# multiMicro_base_64pin.net
KiCad netlist of a schematic drawn in EAGLE
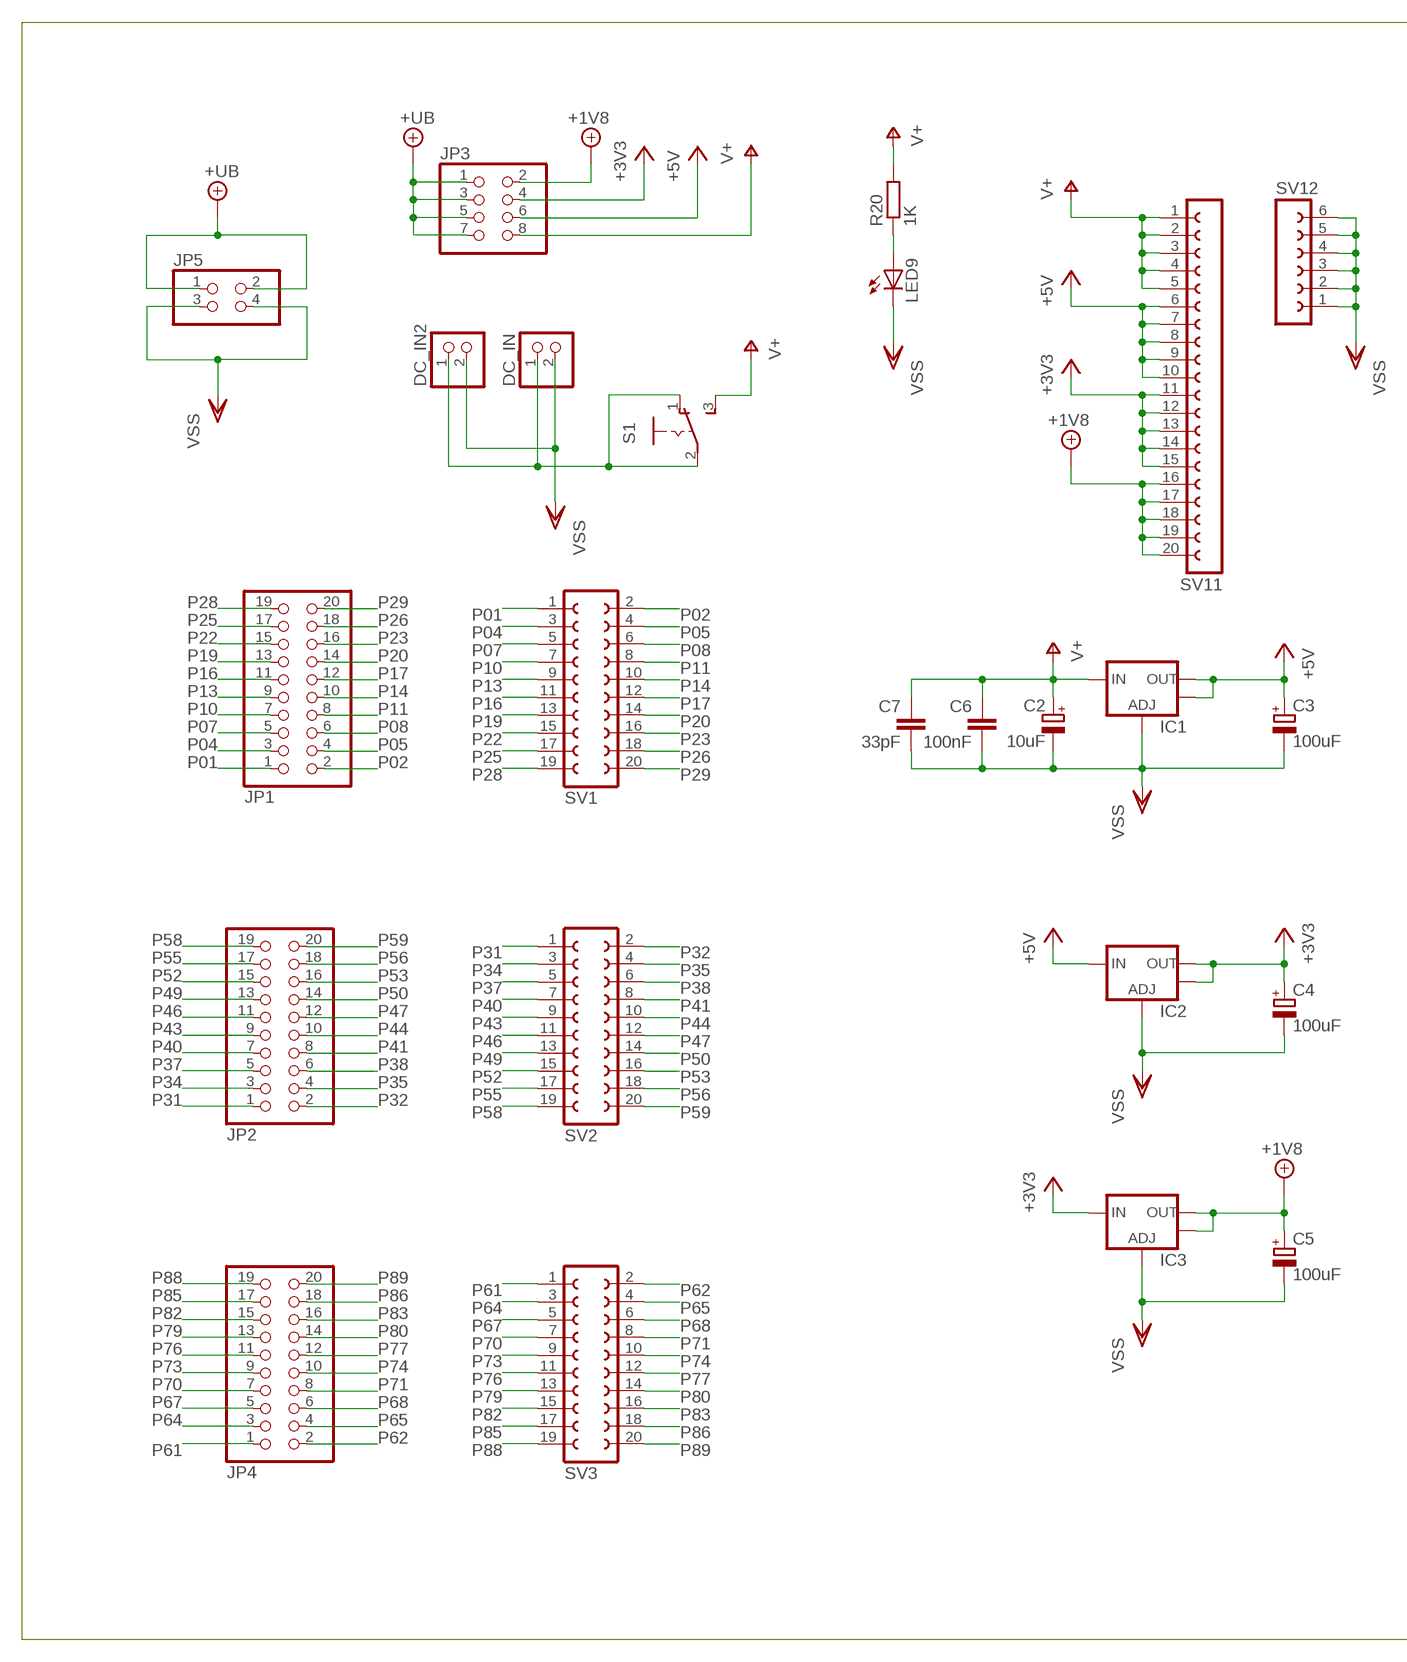
[diagram p0: schematic, sheet 1, part 1 of 2]
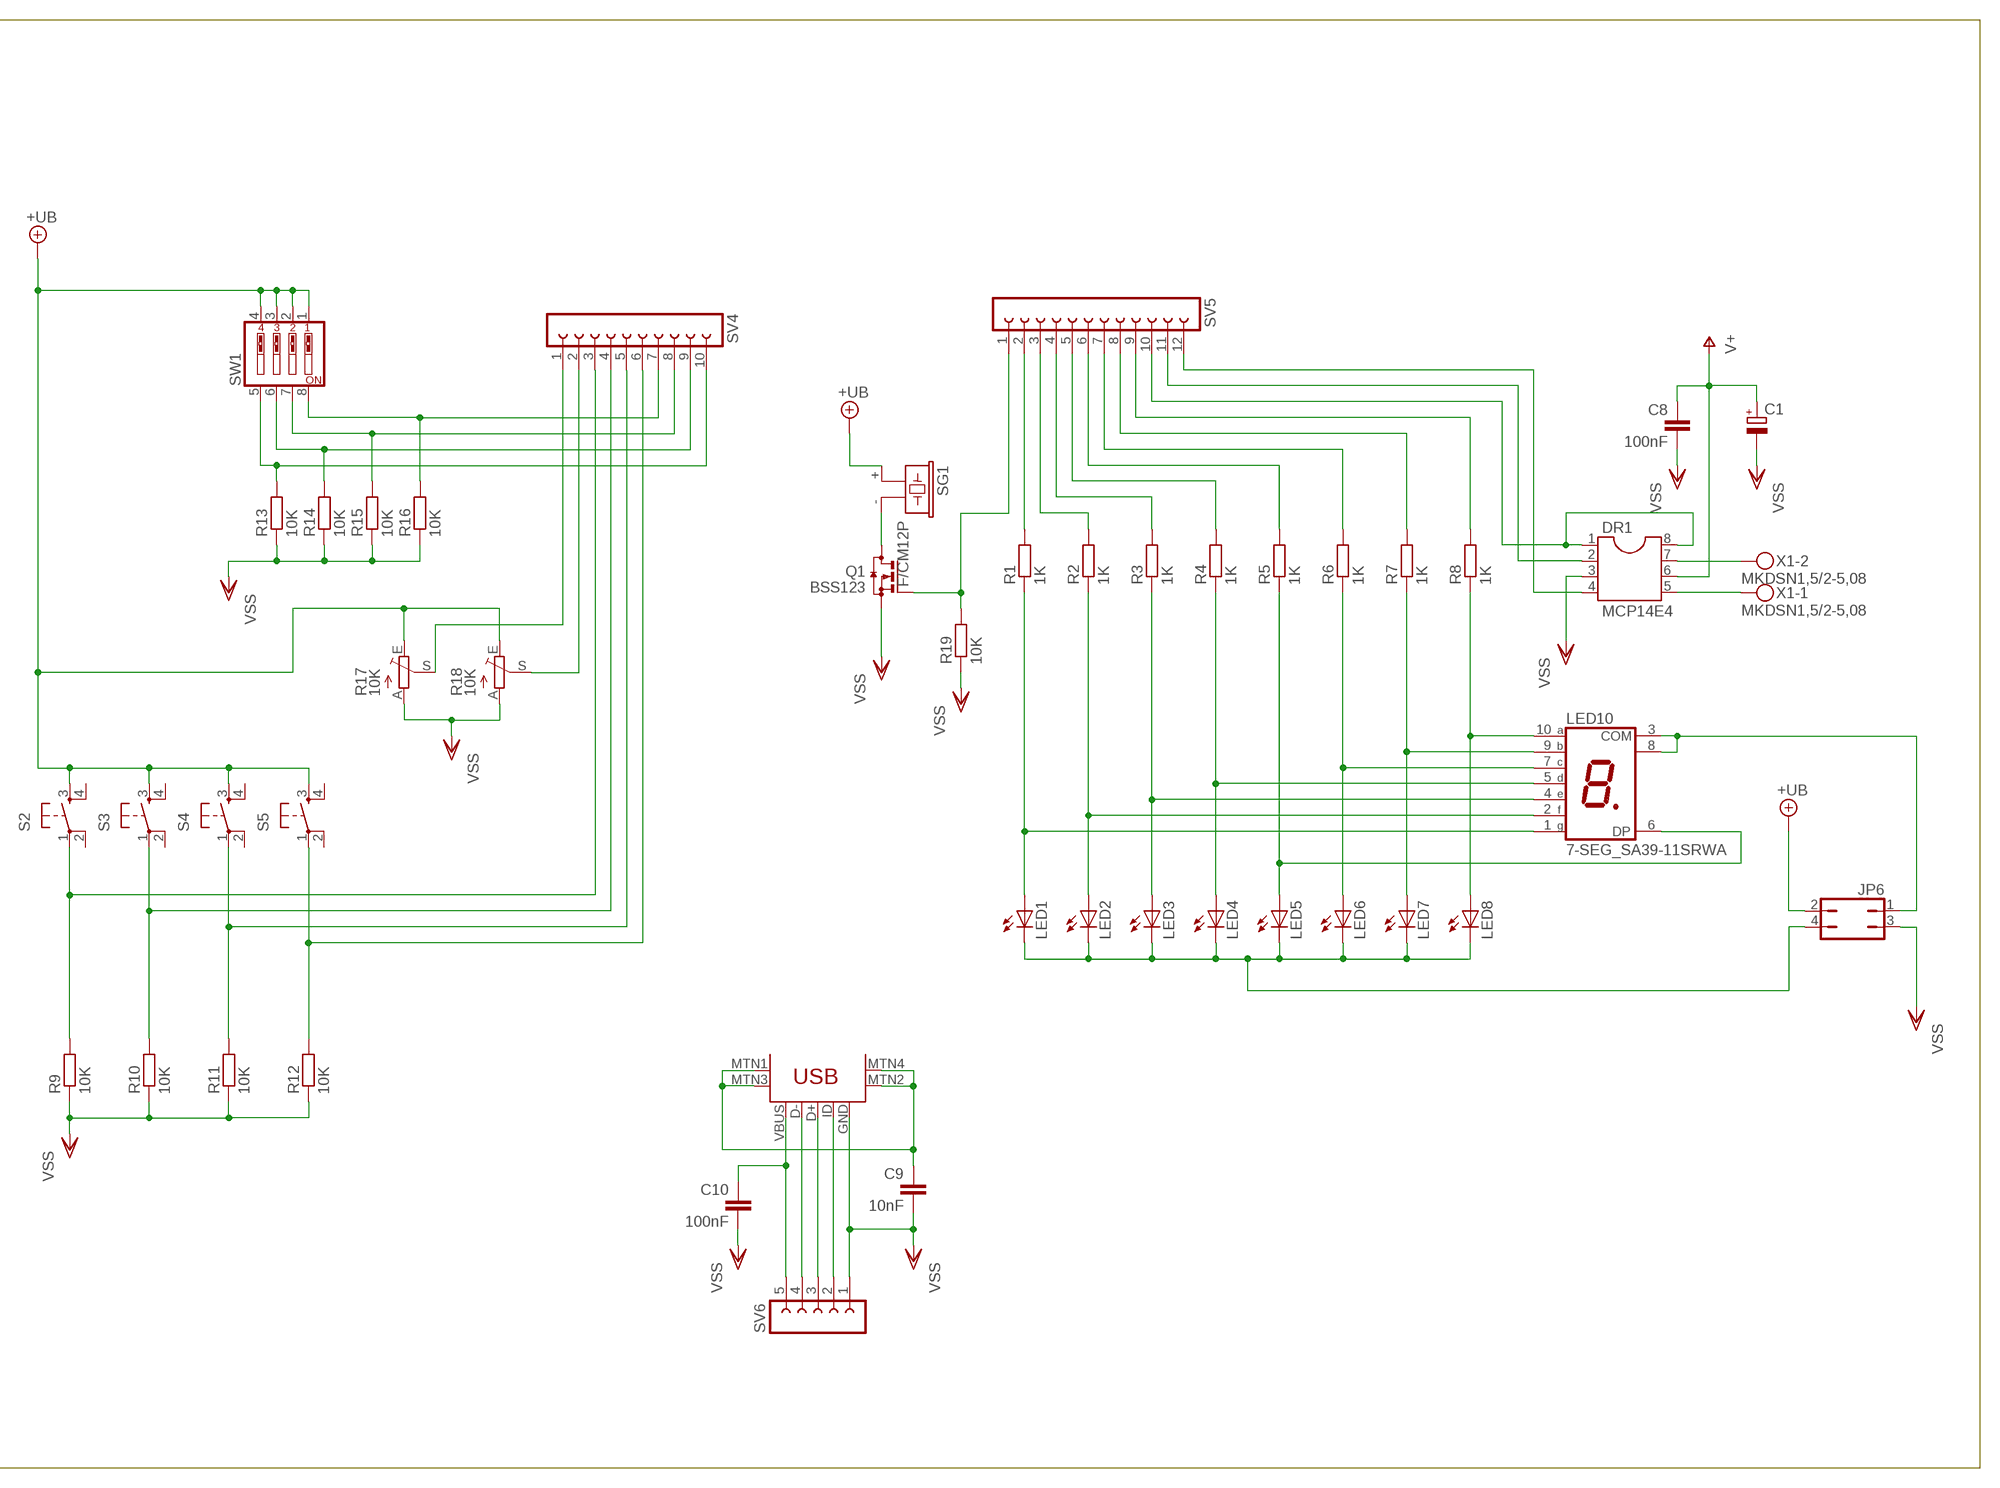
[diagram p1: schematic, sheet 1, part 2 of 2]

(export (version "E")
  (design (tool "Eeschema 10.0.6"))
  (components
    (comp (ref "C1")
      (value "CPOL-EU140CLH-0810")
      (footprint "eagle-import:140CLH-0810")
      (libsource (lib "eagle-import") (part "CPOL-EU140CLH-0810"))
    )
    (comp (ref "C2")
      (value "10uF")
      (footprint "eagle-import:SMC_C")
      (libsource (lib "eagle-import") (part "CPOL-EUSMCC"))
    )
    (comp (ref "C3")
      (value "100uF")
      (footprint "eagle-import:CT7343")
      (libsource (lib "eagle-import") (part "CPOL-EUCT7343"))
    )
    (comp (ref "C4")
      (value "100uF")
      (footprint "eagle-import:CT7343")
      (libsource (lib "eagle-import") (part "CPOL-EUCT7343"))
    )
    (comp (ref "C5")
      (value "100uF")
      (footprint "eagle-import:CT7343")
      (libsource (lib "eagle-import") (part "CPOL-EUCT7343"))
    )
    (comp (ref "C6")
      (value "100nF")
      (footprint "eagle-import:C0805")
      (libsource (lib "eagle-import") (part "C-EUC0805"))
    )
    (comp (ref "C7")
      (value "33pF")
      (footprint "eagle-import:C0805")
      (libsource (lib "eagle-import") (part "C-EUC0805"))
    )
    (comp (ref "C8")
      (value "100nF")
      (footprint "eagle-import:C0805")
      (libsource (lib "eagle-import") (part "C-EUC0805"))
    )
    (comp (ref "C9")
      (value "10nF")
      (footprint "eagle-import:C0805")
      (libsource (lib "eagle-import") (part "C-EUC0805"))
    )
    (comp (ref "C10")
      (value "100nF")
      (footprint "eagle-import:C0805")
      (libsource (lib "eagle-import") (part "C-EUC0805"))
    )
    (comp (ref "DC_IN")
      (value "PINHD-1X2/90")
      (footprint "eagle-import:1X02_90")
      (libsource (lib "eagle-import") (part "PINHD-1X2/90"))
    )
    (comp (ref "DC_IN2")
      (value "PINHD-1X2/90")
      (footprint "eagle-import:1X02_90")
      (libsource (lib "eagle-import") (part "PINHD-1X2/90"))
    )
    (comp (ref "DR1")
      (value "MCP14E4")
      (footprint "eagle-import:SOIC08")
      (libsource (lib "eagle-import") (part "SOIC08"))
    )
    (comp (ref "IC1")
      (value "V_REG_LM1117SOT223")
      (footprint "eagle-import:SOT223")
      (libsource (lib "eagle-import") (part "V_REG_LM1117SOT223"))
    )
    (comp (ref "IC2")
      (value "V_REG_LM1117SOT223")
      (footprint "eagle-import:SOT223")
      (libsource (lib "eagle-import") (part "V_REG_LM1117SOT223"))
    )
    (comp (ref "IC3")
      (value "V_REG_LM1117SOT223")
      (footprint "eagle-import:SOT223")
      (libsource (lib "eagle-import") (part "V_REG_LM1117SOT223"))
    )
    (comp (ref "JP1")
      (value "PINHD-2X10/90")
      (footprint "eagle-import:2X10_90")
      (libsource (lib "eagle-import") (part "PINHD-2X10/90"))
    )
    (comp (ref "JP2")
      (value "PINHD-2X10/90")
      (footprint "eagle-import:2X10_90")
      (libsource (lib "eagle-import") (part "PINHD-2X10/90"))
    )
    (comp (ref "JP3")
      (value "PINHD-2X4")
      (footprint "eagle-import:2X04")
      (libsource (lib "eagle-import") (part "PINHD-2X4"))
    )
    (comp (ref "JP4")
      (value "PINHD-2X10/90")
      (footprint "eagle-import:2X10_90")
      (libsource (lib "eagle-import") (part "PINHD-2X10/90"))
    )
    (comp (ref "JP5")
      (value "PINHD-2X2/90")
      (footprint "eagle-import:2X02_90")
      (libsource (lib "eagle-import") (part "PINHD-2X2/90"))
    )
    (comp (ref "JP6")
      (value "JP2Q")
      (footprint "eagle-import:JP2Q")
      (libsource (lib "eagle-import") (part "JP2Q"))
    )
    (comp (ref "LED1")
      (value "LEDCHIP-LED0805")
      (footprint "eagle-import:CHIP-LED0805")
      (libsource (lib "eagle-import") (part "LEDCHIP-LED0805"))
    )
    (comp (ref "LED2")
      (value "LEDCHIP-LED0805")
      (footprint "eagle-import:CHIP-LED0805")
      (libsource (lib "eagle-import") (part "LEDCHIP-LED0805"))
    )
    (comp (ref "LED3")
      (value "LEDCHIP-LED0805")
      (footprint "eagle-import:CHIP-LED0805")
      (libsource (lib "eagle-import") (part "LEDCHIP-LED0805"))
    )
    (comp (ref "LED4")
      (value "LEDCHIP-LED0805")
      (footprint "eagle-import:CHIP-LED0805")
      (libsource (lib "eagle-import") (part "LEDCHIP-LED0805"))
    )
    (comp (ref "LED5")
      (value "LEDCHIP-LED0805")
      (footprint "eagle-import:CHIP-LED0805")
      (libsource (lib "eagle-import") (part "LEDCHIP-LED0805"))
    )
    (comp (ref "LED6")
      (value "LEDCHIP-LED0805")
      (footprint "eagle-import:CHIP-LED0805")
      (libsource (lib "eagle-import") (part "LEDCHIP-LED0805"))
    )
    (comp (ref "LED7")
      (value "LEDCHIP-LED0805")
      (footprint "eagle-import:CHIP-LED0805")
      (libsource (lib "eagle-import") (part "LEDCHIP-LED0805"))
    )
    (comp (ref "LED8")
      (value "LEDCHIP-LED0805")
      (footprint "eagle-import:CHIP-LED0805")
      (libsource (lib "eagle-import") (part "LEDCHIP-LED0805"))
    )
    (comp (ref "LED9")
      (value "LEDCHIP-LED0805")
      (footprint "eagle-import:CHIP-LED0805")
      (libsource (lib "eagle-import") (part "LEDCHIP-LED0805"))
    )
    (comp (ref "LED10")
      (value "7-SEG_SA39-11SRWA")
      (footprint "eagle-import:SA39-11SRWA")
      (libsource (lib "eagle-import") (part "7-SEG_SA39-11SRWA"))
    )
    (comp (ref "Q1")
      (value "BSS123")
      (footprint "eagle-import:SOT23")
      (libsource (lib "eagle-import") (part "BSS123"))
    )
    (comp (ref "R1")
      (value "1K")
      (footprint "eagle-import:R0805")
      (libsource (lib "eagle-import") (part "R-EU_R0805"))
    )
    (comp (ref "R2")
      (value "1K")
      (footprint "eagle-import:R0805")
      (libsource (lib "eagle-import") (part "R-EU_R0805"))
    )
    (comp (ref "R3")
      (value "1K")
      (footprint "eagle-import:R0805")
      (libsource (lib "eagle-import") (part "R-EU_R0805"))
    )
    (comp (ref "R4")
      (value "1K")
      (footprint "eagle-import:R0805")
      (libsource (lib "eagle-import") (part "R-EU_R0805"))
    )
    (comp (ref "R5")
      (value "1K")
      (footprint "eagle-import:R0805")
      (libsource (lib "eagle-import") (part "R-EU_R0805"))
    )
    (comp (ref "R6")
      (value "1K")
      (footprint "eagle-import:R0805")
      (libsource (lib "eagle-import") (part "R-EU_R0805"))
    )
    (comp (ref "R7")
      (value "1K")
      (footprint "eagle-import:R0805")
      (libsource (lib "eagle-import") (part "R-EU_R0805"))
    )
    (comp (ref "R8")
      (value "1K")
      (footprint "eagle-import:R0805")
      (libsource (lib "eagle-import") (part "R-EU_R0805"))
    )
    (comp (ref "R9")
      (value "10K")
      (footprint "eagle-import:R0805")
      (libsource (lib "eagle-import") (part "R-EU_R0805"))
    )
    (comp (ref "R10")
      (value "10K")
      (footprint "eagle-import:R0805")
      (libsource (lib "eagle-import") (part "R-EU_R0805"))
    )
    (comp (ref "R11")
      (value "10K")
      (footprint "eagle-import:R0805")
      (libsource (lib "eagle-import") (part "R-EU_R0805"))
    )
    (comp (ref "R12")
      (value "10K")
      (footprint "eagle-import:R0805")
      (libsource (lib "eagle-import") (part "R-EU_R0805"))
    )
    (comp (ref "R13")
      (value "10K")
      (footprint "eagle-import:R0805")
      (libsource (lib "eagle-import") (part "R-EU_R0805"))
    )
    (comp (ref "R14")
      (value "10K")
      (footprint "eagle-import:R0805")
      (libsource (lib "eagle-import") (part "R-EU_R0805"))
    )
    (comp (ref "R15")
      (value "10K")
      (footprint "eagle-import:R0805")
      (libsource (lib "eagle-import") (part "R-EU_R0805"))
    )
    (comp (ref "R16")
      (value "10K")
      (footprint "eagle-import:R0805")
      (libsource (lib "eagle-import") (part "R-EU_R0805"))
    )
    (comp (ref "R17")
      (value "10K")
      (footprint "eagle-import:CA6V")
      (libsource (lib "eagle-import") (part "TRIM_EU-CA6V"))
    )
    (comp (ref "R18")
      (value "10K")
      (footprint "eagle-import:CA6V")
      (libsource (lib "eagle-import") (part "TRIM_EU-CA6V"))
    )
    (comp (ref "R19")
      (value "10K")
      (footprint "eagle-import:R0805")
      (libsource (lib "eagle-import") (part "R-EU_R0805"))
    )
    (comp (ref "R20")
      (value "1K")
      (footprint "eagle-import:R0805")
      (libsource (lib "eagle-import") (part "R-EU_R0805"))
    )
    (comp (ref "S1")
      (value "255SB")
      (footprint "eagle-import:255SB")
      (libsource (lib "eagle-import") (part "255SB"))
    )
    (comp (ref "S2")
      (value "TAC_SWITCHPTH")
      (footprint "eagle-import:TACTILE-PTH")
      (libsource (lib "eagle-import") (part "TAC_SWITCHPTH"))
    )
    (comp (ref "S3")
      (value "TAC_SWITCHPTH")
      (footprint "eagle-import:TACTILE-PTH")
      (libsource (lib "eagle-import") (part "TAC_SWITCHPTH"))
    )
    (comp (ref "S4")
      (value "TAC_SWITCHPTH")
      (footprint "eagle-import:TACTILE-PTH")
      (libsource (lib "eagle-import") (part "TAC_SWITCHPTH"))
    )
    (comp (ref "S5")
      (value "TAC_SWITCHPTH")
      (footprint "eagle-import:TACTILE-PTH")
      (libsource (lib "eagle-import") (part "TAC_SWITCHPTH"))
    )
    (comp (ref "SG1")
      (value "F/CM12P")
      (footprint "eagle-import:F_CM12P")
      (libsource (lib "eagle-import") (part "F/CM12P"))
    )
    (comp (ref "SV1")
      (value "FE10-2")
      (footprint "eagle-import:FE10-2")
      (libsource (lib "eagle-import") (part "FE10-2"))
    )
    (comp (ref "SV2")
      (value "FE10-2")
      (footprint "eagle-import:FE10-2")
      (fields (field (name "OC_FARNELL") "unknown") (field (name "OC_NEWARK") "unknown"))
      (libsource (lib "eagle-import") (part "FE10-2"))
    )
    (comp (ref "SV3")
      (value "FE10-2")
      (footprint "eagle-import:FE10-2")
      (fields (field (name "OC_FARNELL") "unknown") (field (name "OC_NEWARK") "unknown"))
      (libsource (lib "eagle-import") (part "FE10-2"))
    )
    (comp (ref "SV4")
      (value "FE10-1")
      (footprint "eagle-import:FE10")
      (libsource (lib "eagle-import") (part "FE10-1"))
    )
    (comp (ref "SV5")
      (value "FE12-1")
      (footprint "eagle-import:FE12")
      (libsource (lib "eagle-import") (part "FE12-1"))
    )
    (comp (ref "SV6")
      (value "FE05-1")
      (footprint "eagle-import:FE05-1")
      (libsource (lib "eagle-import") (part "FE05-1"))
    )
    (comp (ref "SV11")
      (value "FE20-1")
      (footprint "eagle-import:FE20")
      (libsource (lib "eagle-import") (part "FE20-1"))
    )
    (comp (ref "SV12")
      (value "FE06-1")
      (footprint "eagle-import:FE06")
      (libsource (lib "eagle-import") (part "FE06-1"))
    )
    (comp (ref "SW1")
      (value "SW_DIP-4")
      (footprint "eagle-import:EDG-04")
      (libsource (lib "eagle-import") (part "SW_DIP-4"))
    )
    (comp (ref "U$1")
      (value "USB-MINIB-5PIN")
      (footprint "eagle-import:USB-MINIB")
      (libsource (lib "eagle-import") (part "USB-MINIB-5PIN"))
    )
    (comp (ref "X1")
      (value "MKDSN1,5/2-5,08")
      (footprint "eagle-import:MKDSN1,5_2-5,08")
      (fields (field (name "MPN") "MKDSN 1,5/2-5.08"))
      (libsource (lib "eagle-import") (part "MKDSN1,5/2-5,08"))
    )
  )
  (nets
    (net (code "1") (name "+1V8") (class "Default")
      (node (ref "C5") (pin "+") (pinfunction "+_+") (pintype "passive"))
      (node (ref "IC3") (pin "2") (pinfunction "OUT_2") (pintype "output"))
      (node (ref "IC3") (pin "4") (pinfunction "OUT_4") (pintype "output"))
      (node (ref "JP3") (pin "2") (pinfunction "2_2") (pintype "passive"))
      (node (ref "SV11") (pin "16") (pinfunction "16_16") (pintype "passive"))
      (node (ref "SV11") (pin "17") (pinfunction "17_17") (pintype "passive"))
      (node (ref "SV11") (pin "18") (pinfunction "18_18") (pintype "passive"))
      (node (ref "SV11") (pin "19") (pinfunction "19_19") (pintype "passive"))
      (node (ref "SV11") (pin "20") (pinfunction "20_20") (pintype "passive"))
    )
    (net (code "2") (name "+3V3") (class "Default")
      (node (ref "C4") (pin "+") (pinfunction "+_+") (pintype "passive"))
      (node (ref "IC2") (pin "2") (pinfunction "OUT_2") (pintype "output"))
      (node (ref "IC2") (pin "4") (pinfunction "OUT_4") (pintype "output"))
      (node (ref "IC3") (pin "3") (pinfunction "IN_3") (pintype "input"))
      (node (ref "JP3") (pin "4") (pinfunction "4_4") (pintype "passive"))
      (node (ref "SV11") (pin "11") (pinfunction "11_11") (pintype "passive"))
      (node (ref "SV11") (pin "12") (pinfunction "12_12") (pintype "passive"))
      (node (ref "SV11") (pin "13") (pinfunction "13_13") (pintype "passive"))
      (node (ref "SV11") (pin "14") (pinfunction "14_14") (pintype "passive"))
      (node (ref "SV11") (pin "15") (pinfunction "15_15") (pintype "passive"))
    )
    (net (code "3") (name "+5V") (class "Default")
      (node (ref "C3") (pin "+") (pinfunction "+_+") (pintype "passive"))
      (node (ref "IC1") (pin "2") (pinfunction "OUT_2") (pintype "output"))
      (node (ref "IC1") (pin "4") (pinfunction "OUT_4") (pintype "output"))
      (node (ref "IC2") (pin "3") (pinfunction "IN_3") (pintype "input"))
      (node (ref "JP3") (pin "6") (pinfunction "6_6") (pintype "passive"))
      (node (ref "SV11") (pin "10") (pinfunction "10_10") (pintype "passive"))
      (node (ref "SV11") (pin "6") (pinfunction "6_6") (pintype "passive"))
      (node (ref "SV11") (pin "7") (pinfunction "7_7") (pintype "passive"))
      (node (ref "SV11") (pin "8") (pinfunction "8_8") (pintype "passive"))
      (node (ref "SV11") (pin "9") (pinfunction "9_9") (pintype "passive"))
    )
    (net (code "4") (name "+UB") (class "Default")
      (node (ref "JP3") (pin "1") (pinfunction "1_1") (pintype "passive"))
      (node (ref "JP3") (pin "3") (pinfunction "3_3") (pintype "passive"))
      (node (ref "JP3") (pin "5") (pinfunction "5_5") (pintype "passive"))
      (node (ref "JP3") (pin "7") (pinfunction "7_7") (pintype "passive"))
      (node (ref "JP5") (pin "1") (pinfunction "1_1") (pintype "passive"))
      (node (ref "JP5") (pin "2") (pinfunction "2_2") (pintype "passive"))
      (node (ref "JP6") (pin "2") (pinfunction "2_2") (pintype "passive"))
      (node (ref "R17") (pin "E") (pinfunction "E_E") (pintype "passive"))
      (node (ref "R18") (pin "E") (pinfunction "E_E") (pintype "passive"))
      (node (ref "S2") (pin "3") (pinfunction "3_3") (pintype "passive"))
      (node (ref "S3") (pin "3") (pinfunction "3_3") (pintype "passive"))
      (node (ref "S4") (pin "3") (pinfunction "3_3") (pintype "passive"))
      (node (ref "S5") (pin "3") (pinfunction "3_3") (pintype "passive"))
      (node (ref "SG1") (pin "+") (pinfunction "1_+") (pintype "passive"))
      (node (ref "SW1") (pin "1") (pinfunction "1_1") (pintype "passive"))
      (node (ref "SW1") (pin "2") (pinfunction "2_2") (pintype "passive"))
      (node (ref "SW1") (pin "3") (pinfunction "3_3") (pintype "passive"))
      (node (ref "SW1") (pin "4") (pinfunction "4_4") (pintype "passive"))
    )
    (net (code "5") (name "/P01") (class "Default")
      (node (ref "JP1") (pin "1") (pinfunction "1_1") (pintype "passive"))
      (node (ref "SV1") (pin "1") (pinfunction "1_1") (pintype "passive"))
    )
    (net (code "6") (name "/P02") (class "Default")
      (node (ref "JP1") (pin "2") (pinfunction "2_2") (pintype "passive"))
      (node (ref "SV1") (pin "2") (pinfunction "2_2") (pintype "passive"))
    )
    (net (code "7") (name "/P04") (class "Default")
      (node (ref "JP1") (pin "3") (pinfunction "3_3") (pintype "passive"))
      (node (ref "SV1") (pin "3") (pinfunction "3_3") (pintype "passive"))
    )
    (net (code "8") (name "/P05") (class "Default")
      (node (ref "JP1") (pin "4") (pinfunction "4_4") (pintype "passive"))
      (node (ref "SV1") (pin "4") (pinfunction "4_4") (pintype "passive"))
    )
    (net (code "9") (name "/P07") (class "Default")
      (node (ref "JP1") (pin "5") (pinfunction "5_5") (pintype "passive"))
      (node (ref "SV1") (pin "5") (pinfunction "5_5") (pintype "passive"))
    )
    (net (code "10") (name "/P08") (class "Default")
      (node (ref "JP1") (pin "6") (pinfunction "6_6") (pintype "passive"))
      (node (ref "SV1") (pin "6") (pinfunction "6_6") (pintype "passive"))
    )
    (net (code "11") (name "/P10") (class "Default")
      (node (ref "JP1") (pin "7") (pinfunction "7_7") (pintype "passive"))
      (node (ref "SV1") (pin "7") (pinfunction "7_7") (pintype "passive"))
    )
    (net (code "12") (name "/P11") (class "Default")
      (node (ref "JP1") (pin "8") (pinfunction "8_8") (pintype "passive"))
      (node (ref "SV1") (pin "8") (pinfunction "8_8") (pintype "passive"))
    )
    (net (code "13") (name "/P13") (class "Default")
      (node (ref "JP1") (pin "9") (pinfunction "9_9") (pintype "passive"))
      (node (ref "SV1") (pin "9") (pinfunction "9_9") (pintype "passive"))
    )
    (net (code "14") (name "/P14") (class "Default")
      (node (ref "JP1") (pin "10") (pinfunction "10_10") (pintype "passive"))
      (node (ref "SV1") (pin "10") (pinfunction "10_10") (pintype "passive"))
    )
    (net (code "15") (name "/P16") (class "Default")
      (node (ref "JP1") (pin "11") (pinfunction "11_11") (pintype "passive"))
      (node (ref "SV1") (pin "11") (pinfunction "11_11") (pintype "passive"))
    )
    (net (code "16") (name "/P17") (class "Default")
      (node (ref "JP1") (pin "12") (pinfunction "12_12") (pintype "passive"))
      (node (ref "SV1") (pin "12") (pinfunction "12_12") (pintype "passive"))
    )
    (net (code "17") (name "/P19") (class "Default")
      (node (ref "JP1") (pin "13") (pinfunction "13_13") (pintype "passive"))
      (node (ref "SV1") (pin "13") (pinfunction "13_13") (pintype "passive"))
    )
    (net (code "18") (name "/P20") (class "Default")
      (node (ref "JP1") (pin "14") (pinfunction "14_14") (pintype "passive"))
      (node (ref "SV1") (pin "14") (pinfunction "14_14") (pintype "passive"))
    )
    (net (code "19") (name "/P22") (class "Default")
      (node (ref "JP1") (pin "15") (pinfunction "15_15") (pintype "passive"))
      (node (ref "SV1") (pin "15") (pinfunction "15_15") (pintype "passive"))
    )
    (net (code "20") (name "/P23") (class "Default")
      (node (ref "JP1") (pin "16") (pinfunction "16_16") (pintype "passive"))
      (node (ref "SV1") (pin "16") (pinfunction "16_16") (pintype "passive"))
    )
    (net (code "21") (name "/P25") (class "Default")
      (node (ref "JP1") (pin "17") (pinfunction "17_17") (pintype "passive"))
      (node (ref "SV1") (pin "17") (pinfunction "17_17") (pintype "passive"))
    )
    (net (code "22") (name "/P26") (class "Default")
      (node (ref "JP1") (pin "18") (pinfunction "18_18") (pintype "passive"))
      (node (ref "SV1") (pin "18") (pinfunction "18_18") (pintype "passive"))
    )
    (net (code "23") (name "/P28") (class "Default")
      (node (ref "JP1") (pin "19") (pinfunction "19_19") (pintype "passive"))
      (node (ref "SV1") (pin "19") (pinfunction "19_19") (pintype "passive"))
    )
    (net (code "24") (name "/P29") (class "Default")
      (node (ref "JP1") (pin "20") (pinfunction "20_20") (pintype "passive"))
      (node (ref "SV1") (pin "20") (pinfunction "20_20") (pintype "passive"))
    )
    (net (code "25") (name "/P31") (class "Default")
      (node (ref "JP2") (pin "1") (pinfunction "1_1") (pintype "passive"))
      (node (ref "SV2") (pin "1") (pinfunction "1_1") (pintype "passive"))
    )
    (net (code "26") (name "/P32") (class "Default")
      (node (ref "JP2") (pin "2") (pinfunction "2_2") (pintype "passive"))
      (node (ref "SV2") (pin "2") (pinfunction "2_2") (pintype "passive"))
    )
    (net (code "27") (name "/P34") (class "Default")
      (node (ref "JP2") (pin "3") (pinfunction "3_3") (pintype "passive"))
      (node (ref "SV2") (pin "3") (pinfunction "3_3") (pintype "passive"))
    )
    (net (code "28") (name "/P35") (class "Default")
      (node (ref "JP2") (pin "4") (pinfunction "4_4") (pintype "passive"))
      (node (ref "SV2") (pin "4") (pinfunction "4_4") (pintype "passive"))
    )
    (net (code "29") (name "/P37") (class "Default")
      (node (ref "JP2") (pin "5") (pinfunction "5_5") (pintype "passive"))
      (node (ref "SV2") (pin "5") (pinfunction "5_5") (pintype "passive"))
    )
    (net (code "30") (name "/P38") (class "Default")
      (node (ref "JP2") (pin "6") (pinfunction "6_6") (pintype "passive"))
      (node (ref "SV2") (pin "6") (pinfunction "6_6") (pintype "passive"))
    )
    (net (code "31") (name "/P40") (class "Default")
      (node (ref "JP2") (pin "7") (pinfunction "7_7") (pintype "passive"))
      (node (ref "SV2") (pin "7") (pinfunction "7_7") (pintype "passive"))
    )
    (net (code "32") (name "/P41") (class "Default")
      (node (ref "JP2") (pin "8") (pinfunction "8_8") (pintype "passive"))
      (node (ref "SV2") (pin "8") (pinfunction "8_8") (pintype "passive"))
    )
    (net (code "33") (name "/P43") (class "Default")
      (node (ref "JP2") (pin "9") (pinfunction "9_9") (pintype "passive"))
      (node (ref "SV2") (pin "9") (pinfunction "9_9") (pintype "passive"))
    )
    (net (code "34") (name "/P44") (class "Default")
      (node (ref "JP2") (pin "10") (pinfunction "10_10") (pintype "passive"))
      (node (ref "SV2") (pin "10") (pinfunction "10_10") (pintype "passive"))
    )
    (net (code "35") (name "/P46") (class "Default")
      (node (ref "JP2") (pin "11") (pinfunction "11_11") (pintype "passive"))
      (node (ref "SV2") (pin "11") (pinfunction "11_11") (pintype "passive"))
    )
    (net (code "36") (name "/P47") (class "Default")
      (node (ref "JP2") (pin "12") (pinfunction "12_12") (pintype "passive"))
      (node (ref "SV2") (pin "12") (pinfunction "12_12") (pintype "passive"))
    )
    (net (code "37") (name "/P49") (class "Default")
      (node (ref "JP2") (pin "13") (pinfunction "13_13") (pintype "passive"))
      (node (ref "SV2") (pin "13") (pinfunction "13_13") (pintype "passive"))
    )
    (net (code "38") (name "/P50") (class "Default")
      (node (ref "JP2") (pin "14") (pinfunction "14_14") (pintype "passive"))
      (node (ref "SV2") (pin "14") (pinfunction "14_14") (pintype "passive"))
    )
    (net (code "39") (name "/P52") (class "Default")
      (node (ref "JP2") (pin "15") (pinfunction "15_15") (pintype "passive"))
      (node (ref "SV2") (pin "15") (pinfunction "15_15") (pintype "passive"))
    )
    (net (code "40") (name "/P53") (class "Default")
      (node (ref "JP2") (pin "16") (pinfunction "16_16") (pintype "passive"))
      (node (ref "SV2") (pin "16") (pinfunction "16_16") (pintype "passive"))
    )
    (net (code "41") (name "/P55") (class "Default")
      (node (ref "JP2") (pin "17") (pinfunction "17_17") (pintype "passive"))
      (node (ref "SV2") (pin "17") (pinfunction "17_17") (pintype "passive"))
    )
    (net (code "42") (name "/P56") (class "Default")
      (node (ref "JP2") (pin "18") (pinfunction "18_18") (pintype "passive"))
      (node (ref "SV2") (pin "18") (pinfunction "18_18") (pintype "passive"))
    )
    (net (code "43") (name "/P58") (class "Default")
      (node (ref "JP2") (pin "19") (pinfunction "19_19") (pintype "passive"))
      (node (ref "SV2") (pin "19") (pinfunction "19_19") (pintype "passive"))
    )
    (net (code "44") (name "/P59") (class "Default")
      (node (ref "JP2") (pin "20") (pinfunction "20_20") (pintype "passive"))
      (node (ref "SV2") (pin "20") (pinfunction "20_20") (pintype "passive"))
    )
    (net (code "45") (name "/P61") (class "Default")
      (node (ref "JP4") (pin "1") (pinfunction "1_1") (pintype "passive"))
      (node (ref "SV3") (pin "1") (pinfunction "1_1") (pintype "passive"))
    )
    (net (code "46") (name "/P62") (class "Default")
      (node (ref "JP4") (pin "2") (pinfunction "2_2") (pintype "passive"))
      (node (ref "SV3") (pin "2") (pinfunction "2_2") (pintype "passive"))
    )
    (net (code "47") (name "/P64") (class "Default")
      (node (ref "JP4") (pin "3") (pinfunction "3_3") (pintype "passive"))
      (node (ref "SV3") (pin "3") (pinfunction "3_3") (pintype "passive"))
    )
    (net (code "48") (name "/P65") (class "Default")
      (node (ref "JP4") (pin "4") (pinfunction "4_4") (pintype "passive"))
      (node (ref "SV3") (pin "4") (pinfunction "4_4") (pintype "passive"))
    )
    (net (code "49") (name "/P67") (class "Default")
      (node (ref "JP4") (pin "5") (pinfunction "5_5") (pintype "passive"))
      (node (ref "SV3") (pin "5") (pinfunction "5_5") (pintype "passive"))
    )
    (net (code "50") (name "/P68") (class "Default")
      (node (ref "JP4") (pin "6") (pinfunction "6_6") (pintype "passive"))
      (node (ref "SV3") (pin "6") (pinfunction "6_6") (pintype "passive"))
    )
    (net (code "51") (name "/P70") (class "Default")
      (node (ref "JP4") (pin "7") (pinfunction "7_7") (pintype "passive"))
      (node (ref "SV3") (pin "7") (pinfunction "7_7") (pintype "passive"))
    )
    (net (code "52") (name "/P71") (class "Default")
      (node (ref "JP4") (pin "8") (pinfunction "8_8") (pintype "passive"))
      (node (ref "SV3") (pin "8") (pinfunction "8_8") (pintype "passive"))
    )
    (net (code "53") (name "/P73") (class "Default")
      (node (ref "JP4") (pin "9") (pinfunction "9_9") (pintype "passive"))
      (node (ref "SV3") (pin "9") (pinfunction "9_9") (pintype "passive"))
    )
    (net (code "54") (name "/P74") (class "Default")
      (node (ref "JP4") (pin "10") (pinfunction "10_10") (pintype "passive"))
      (node (ref "SV3") (pin "10") (pinfunction "10_10") (pintype "passive"))
    )
    (net (code "55") (name "/P76") (class "Default")
      (node (ref "JP4") (pin "11") (pinfunction "11_11") (pintype "passive"))
      (node (ref "SV3") (pin "11") (pinfunction "11_11") (pintype "passive"))
    )
    (net (code "56") (name "/P77") (class "Default")
      (node (ref "JP4") (pin "12") (pinfunction "12_12") (pintype "passive"))
      (node (ref "SV3") (pin "12") (pinfunction "12_12") (pintype "passive"))
    )
    (net (code "57") (name "/P79") (class "Default")
      (node (ref "JP4") (pin "13") (pinfunction "13_13") (pintype "passive"))
      (node (ref "SV3") (pin "13") (pinfunction "13_13") (pintype "passive"))
    )
    (net (code "58") (name "/P80") (class "Default")
      (node (ref "JP4") (pin "14") (pinfunction "14_14") (pintype "passive"))
      (node (ref "SV3") (pin "14") (pinfunction "14_14") (pintype "passive"))
    )
    (net (code "59") (name "/P82") (class "Default")
      (node (ref "JP4") (pin "15") (pinfunction "15_15") (pintype "passive"))
      (node (ref "SV3") (pin "15") (pinfunction "15_15") (pintype "passive"))
    )
    (net (code "60") (name "/P83") (class "Default")
      (node (ref "JP4") (pin "16") (pinfunction "16_16") (pintype "passive"))
      (node (ref "SV3") (pin "16") (pinfunction "16_16") (pintype "passive"))
    )
    (net (code "61") (name "/P85") (class "Default")
      (node (ref "JP4") (pin "17") (pinfunction "17_17") (pintype "passive"))
      (node (ref "SV3") (pin "17") (pinfunction "17_17") (pintype "passive"))
    )
    (net (code "62") (name "/P86") (class "Default")
      (node (ref "JP4") (pin "18") (pinfunction "18_18") (pintype "passive"))
      (node (ref "SV3") (pin "18") (pinfunction "18_18") (pintype "passive"))
    )
    (net (code "63") (name "/P88") (class "Default")
      (node (ref "JP4") (pin "19") (pinfunction "19_19") (pintype "passive"))
      (node (ref "SV3") (pin "19") (pinfunction "19_19") (pintype "passive"))
    )
    (net (code "64") (name "/P89") (class "Default")
      (node (ref "JP4") (pin "20") (pinfunction "20_20") (pintype "passive"))
      (node (ref "SV3") (pin "20") (pinfunction "20_20") (pintype "passive"))
    )
    (net (code "65") (name "Net-(C10-Pad1)") (class "Default")
      (node (ref "C10") (pin "1") (pinfunction "1_1") (pintype "passive"))
      (node (ref "SV6") (pin "5") (pinfunction "5_5") (pintype "passive"))
      (node (ref "U$1") (pin "VBUS") (pinfunction "VBUS_VBUS") (pintype "bidirectional"))
    )
    (net (code "66") (name "Net-(DR1-Pad1)") (class "Default")
      (node (ref "DR1") (pin "1") (pinfunction "1_1") (pintype "passive"))
      (node (ref "DR1") (pin "8") (pinfunction "8_8") (pintype "passive"))
      (node (ref "SV5") (pin "10") (pinfunction "10_10") (pintype "passive"))
    )
    (net (code "67") (name "Net-(DR1-Pad2)") (class "Default")
      (node (ref "DR1") (pin "2") (pinfunction "2_2") (pintype "passive"))
      (node (ref "SV5") (pin "11") (pinfunction "11_11") (pintype "passive"))
    )
    (net (code "68") (name "Net-(DR1-Pad4)") (class "Default")
      (node (ref "DR1") (pin "4") (pinfunction "4_4") (pintype "passive"))
      (node (ref "SV5") (pin "12") (pinfunction "12_12") (pintype "passive"))
    )
    (net (code "69") (name "Net-(JP6-Pad1)") (class "Default")
      (node (ref "JP6") (pin "1") (pinfunction "1_1") (pintype "passive"))
      (node (ref "LED10") (pin "3") (pinfunction "COM_3") (pintype "passive"))
      (node (ref "LED10") (pin "8") (pinfunction "COM_8") (pintype "passive"))
    )
    (net (code "70") (name "Net-(JP6-Pad4)") (class "Default")
      (node (ref "JP6") (pin "4") (pinfunction "4_4") (pintype "passive"))
      (node (ref "LED1") (pin "C") (pinfunction "C_C") (pintype "passive"))
      (node (ref "LED2") (pin "C") (pinfunction "C_C") (pintype "passive"))
      (node (ref "LED3") (pin "C") (pinfunction "C_C") (pintype "passive"))
      (node (ref "LED4") (pin "C") (pinfunction "C_C") (pintype "passive"))
      (node (ref "LED5") (pin "C") (pinfunction "C_C") (pintype "passive"))
      (node (ref "LED6") (pin "C") (pinfunction "C_C") (pintype "passive"))
      (node (ref "LED7") (pin "C") (pinfunction "C_C") (pintype "passive"))
      (node (ref "LED8") (pin "C") (pinfunction "C_C") (pintype "passive"))
    )
    (net (code "71") (name "Net-(LED9-PadA)") (class "Default")
      (node (ref "LED9") (pin "A") (pinfunction "A_A") (pintype "passive"))
      (node (ref "R20") (pin "1") (pinfunction "1_1") (pintype "passive"))
    )
    (net (code "72") (name "Net-(LED10-A)") (class "Default")
      (node (ref "LED10") (pin "10") (pinfunction "A_10") (pintype "passive"))
      (node (ref "LED8") (pin "A") (pinfunction "A_A") (pintype "passive"))
      (node (ref "R8") (pin "1") (pinfunction "1_1") (pintype "passive"))
    )
    (net (code "73") (name "Net-(LED10-B)") (class "Default")
      (node (ref "LED10") (pin "9") (pinfunction "B_9") (pintype "passive"))
      (node (ref "LED7") (pin "A") (pinfunction "A_A") (pintype "passive"))
      (node (ref "R7") (pin "1") (pinfunction "1_1") (pintype "passive"))
    )
    (net (code "74") (name "Net-(LED10-C)") (class "Default")
      (node (ref "LED10") (pin "7") (pinfunction "C_7") (pintype "passive"))
      (node (ref "LED6") (pin "A") (pinfunction "A_A") (pintype "passive"))
      (node (ref "R6") (pin "1") (pinfunction "1_1") (pintype "passive"))
    )
    (net (code "75") (name "Net-(LED10-D)") (class "Default")
      (node (ref "LED10") (pin "5") (pinfunction "D_5") (pintype "passive"))
      (node (ref "LED4") (pin "A") (pinfunction "A_A") (pintype "passive"))
      (node (ref "R4") (pin "1") (pinfunction "1_1") (pintype "passive"))
    )
    (net (code "76") (name "Net-(LED10-DP)") (class "Default")
      (node (ref "LED10") (pin "6") (pinfunction "DP_6") (pintype "passive"))
      (node (ref "LED5") (pin "A") (pinfunction "A_A") (pintype "passive"))
      (node (ref "R5") (pin "1") (pinfunction "1_1") (pintype "passive"))
    )
    (net (code "77") (name "Net-(LED10-E)") (class "Default")
      (node (ref "LED10") (pin "4") (pinfunction "E_4") (pintype "passive"))
      (node (ref "LED3") (pin "A") (pinfunction "A_A") (pintype "passive"))
      (node (ref "R3") (pin "1") (pinfunction "1_1") (pintype "passive"))
    )
    (net (code "78") (name "Net-(LED10-F)") (class "Default")
      (node (ref "LED10") (pin "2") (pinfunction "F_2") (pintype "passive"))
      (node (ref "LED2") (pin "A") (pinfunction "A_A") (pintype "passive"))
      (node (ref "R2") (pin "1") (pinfunction "1_1") (pintype "passive"))
    )
    (net (code "79") (name "Net-(LED10-G)") (class "Default")
      (node (ref "LED1") (pin "A") (pinfunction "A_A") (pintype "passive"))
      (node (ref "LED10") (pin "1") (pinfunction "G_1") (pintype "passive"))
      (node (ref "R1") (pin "1") (pinfunction "1_1") (pintype "passive"))
    )
    (net (code "80") (name "Net-(Q1-D)") (class "Default")
      (node (ref "Q1") (pin "3") (pinfunction "D_3") (pintype "passive"))
      (node (ref "SG1") (pin "-") (pinfunction "2_-") (pintype "passive"))
    )
    (net (code "81") (name "Net-(Q1-G)") (class "Default")
      (node (ref "Q1") (pin "1") (pinfunction "G_1") (pintype "passive"))
      (node (ref "R19") (pin "2") (pinfunction "2_2") (pintype "passive"))
      (node (ref "SV5") (pin "1") (pinfunction "1_1") (pintype "passive"))
    )
    (net (code "82") (name "Net-(R1-Pad2)") (class "Default")
      (node (ref "R1") (pin "2") (pinfunction "2_2") (pintype "passive"))
      (node (ref "SV5") (pin "2") (pinfunction "2_2") (pintype "passive"))
    )
    (net (code "83") (name "Net-(R2-Pad2)") (class "Default")
      (node (ref "R2") (pin "2") (pinfunction "2_2") (pintype "passive"))
      (node (ref "SV5") (pin "3") (pinfunction "3_3") (pintype "passive"))
    )
    (net (code "84") (name "Net-(R3-Pad2)") (class "Default")
      (node (ref "R3") (pin "2") (pinfunction "2_2") (pintype "passive"))
      (node (ref "SV5") (pin "4") (pinfunction "4_4") (pintype "passive"))
    )
    (net (code "85") (name "Net-(R4-Pad2)") (class "Default")
      (node (ref "R4") (pin "2") (pinfunction "2_2") (pintype "passive"))
      (node (ref "SV5") (pin "5") (pinfunction "5_5") (pintype "passive"))
    )
    (net (code "86") (name "Net-(R5-Pad2)") (class "Default")
      (node (ref "R5") (pin "2") (pinfunction "2_2") (pintype "passive"))
      (node (ref "SV5") (pin "6") (pinfunction "6_6") (pintype "passive"))
    )
    (net (code "87") (name "Net-(R6-Pad2)") (class "Default")
      (node (ref "R6") (pin "2") (pinfunction "2_2") (pintype "passive"))
      (node (ref "SV5") (pin "7") (pinfunction "7_7") (pintype "passive"))
    )
    (net (code "88") (name "Net-(R7-Pad2)") (class "Default")
      (node (ref "R7") (pin "2") (pinfunction "2_2") (pintype "passive"))
      (node (ref "SV5") (pin "8") (pinfunction "8_8") (pintype "passive"))
    )
    (net (code "89") (name "Net-(R8-Pad2)") (class "Default")
      (node (ref "R8") (pin "2") (pinfunction "2_2") (pintype "passive"))
      (node (ref "SV5") (pin "9") (pinfunction "9_9") (pintype "passive"))
    )
    (net (code "90") (name "Net-(R9-Pad2)") (class "Default")
      (node (ref "R9") (pin "2") (pinfunction "2_2") (pintype "passive"))
      (node (ref "S2") (pin "1") (pinfunction "1_1") (pintype "passive"))
      (node (ref "SV4") (pin "3") (pinfunction "3_3") (pintype "passive"))
    )
    (net (code "91") (name "Net-(R10-Pad2)") (class "Default")
      (node (ref "R10") (pin "2") (pinfunction "2_2") (pintype "passive"))
      (node (ref "S3") (pin "1") (pinfunction "1_1") (pintype "passive"))
      (node (ref "SV4") (pin "4") (pinfunction "4_4") (pintype "passive"))
    )
    (net (code "92") (name "Net-(R11-Pad2)") (class "Default")
      (node (ref "R11") (pin "2") (pinfunction "2_2") (pintype "passive"))
      (node (ref "S4") (pin "1") (pinfunction "1_1") (pintype "passive"))
      (node (ref "SV4") (pin "5") (pinfunction "5_5") (pintype "passive"))
    )
    (net (code "93") (name "Net-(R12-Pad2)") (class "Default")
      (node (ref "R12") (pin "2") (pinfunction "2_2") (pintype "passive"))
      (node (ref "S5") (pin "1") (pinfunction "1_1") (pintype "passive"))
      (node (ref "SV4") (pin "6") (pinfunction "6_6") (pintype "passive"))
    )
    (net (code "94") (name "Net-(R13-Pad2)") (class "Default")
      (node (ref "R13") (pin "2") (pinfunction "2_2") (pintype "passive"))
      (node (ref "SV4") (pin "10") (pinfunction "10_10") (pintype "passive"))
      (node (ref "SW1") (pin "5") (pinfunction "5_5") (pintype "passive"))
    )
    (net (code "95") (name "Net-(R14-Pad2)") (class "Default")
      (node (ref "R14") (pin "2") (pinfunction "2_2") (pintype "passive"))
      (node (ref "SV4") (pin "9") (pinfunction "9_9") (pintype "passive"))
      (node (ref "SW1") (pin "6") (pinfunction "6_6") (pintype "passive"))
    )
    (net (code "96") (name "Net-(R15-Pad2)") (class "Default")
      (node (ref "R15") (pin "2") (pinfunction "2_2") (pintype "passive"))
      (node (ref "SV4") (pin "8") (pinfunction "8_8") (pintype "passive"))
      (node (ref "SW1") (pin "7") (pinfunction "7_7") (pintype "passive"))
    )
    (net (code "97") (name "Net-(R16-Pad2)") (class "Default")
      (node (ref "R16") (pin "2") (pinfunction "2_2") (pintype "passive"))
      (node (ref "SV4") (pin "7") (pinfunction "7_7") (pintype "passive"))
      (node (ref "SW1") (pin "8") (pinfunction "8_8") (pintype "passive"))
    )
    (net (code "98") (name "Net-(R17-PadS)") (class "Default")
      (node (ref "R17") (pin "S") (pinfunction "S_S") (pintype "passive"))
      (node (ref "SV4") (pin "1") (pinfunction "1_1") (pintype "passive"))
    )
    (net (code "99") (name "Net-(R18-PadS)") (class "Default")
      (node (ref "R18") (pin "S") (pinfunction "S_S") (pintype "passive"))
      (node (ref "SV4") (pin "2") (pinfunction "2_2") (pintype "passive"))
    )
    (net (code "100") (name "Net-(S1-O)") (class "Default")
      (node (ref "DC_IN") (pin "1") (pinfunction "1_1") (pintype "passive"))
      (node (ref "DC_IN2") (pin "1") (pinfunction "1_1") (pintype "passive"))
      (node (ref "S1") (pin "1") (pinfunction "O_1") (pintype "passive"))
      (node (ref "S1") (pin "2") (pinfunction "P_2") (pintype "passive"))
    )
    (net (code "101") (name "Net-(SV6-Pad2)") (class "Default")
      (node (ref "SV6") (pin "2") (pinfunction "2_2") (pintype "passive"))
      (node (ref "U$1") (pin "ID") (pinfunction "ID_ID") (pintype "bidirectional"))
    )
    (net (code "102") (name "Net-(SV6-Pad3)") (class "Default")
      (node (ref "SV6") (pin "3") (pinfunction "3_3") (pintype "passive"))
      (node (ref "U$1") (pin "D+") (pinfunction "D+_D+") (pintype "bidirectional"))
    )
    (net (code "103") (name "Net-(SV6-Pad4)") (class "Default")
      (node (ref "SV6") (pin "4") (pinfunction "4_4") (pintype "passive"))
      (node (ref "U$1") (pin "D-") (pinfunction "D-_D-") (pintype "bidirectional"))
    )
    (net (code "104") (name "Net-(U$1-MTN1)") (class "Default")
      (node (ref "C9") (pin "1") (pinfunction "1_1") (pintype "passive"))
      (node (ref "U$1") (pin "MTN1") (pinfunction "MTN2_MTN1") (pintype "bidirectional"))
      (node (ref "U$1") (pin "MTN2") (pinfunction "MTN3_MTN2") (pintype "bidirectional"))
      (node (ref "U$1") (pin "MTN3") (pinfunction "MTN1_MTN3") (pintype "bidirectional"))
      (node (ref "U$1") (pin "MTN4") (pinfunction "MTN4_MTN4") (pintype "bidirectional"))
    )
    (net (code "105") (name "Net-(X1A-KL)") (class "Default")
      (node (ref "DR1") (pin "5") (pinfunction "5_5") (pintype "passive"))
      (node (ref "X1") (pin "1") (pinfunction "KL_1") (pintype "passive"))
    )
    (net (code "106") (name "Net-(X1B-KL)") (class "Default")
      (node (ref "DR1") (pin "7") (pinfunction "7_7") (pintype "passive"))
      (node (ref "X1") (pin "2") (pinfunction "KL_2") (pintype "passive"))
    )
    (net (code "107") (name "V+") (class "Default")
      (node (ref "C1") (pin "+") (pinfunction "+_+") (pintype "passive"))
      (node (ref "C2") (pin "+") (pinfunction "+_+") (pintype "passive"))
      (node (ref "C6") (pin "1") (pinfunction "1_1") (pintype "passive"))
      (node (ref "C7") (pin "1") (pinfunction "1_1") (pintype "passive"))
      (node (ref "C8") (pin "1") (pinfunction "1_1") (pintype "passive"))
      (node (ref "DR1") (pin "6") (pinfunction "6_6") (pintype "passive"))
      (node (ref "IC1") (pin "3") (pinfunction "IN_3") (pintype "input"))
      (node (ref "JP3") (pin "8") (pinfunction "8_8") (pintype "passive"))
      (node (ref "R20") (pin "2") (pinfunction "2_2") (pintype "passive"))
      (node (ref "S1") (pin "3") (pinfunction "S_3") (pintype "passive"))
      (node (ref "SV11") (pin "1") (pinfunction "1_1") (pintype "passive"))
      (node (ref "SV11") (pin "2") (pinfunction "2_2") (pintype "passive"))
      (node (ref "SV11") (pin "3") (pinfunction "3_3") (pintype "passive"))
      (node (ref "SV11") (pin "4") (pinfunction "4_4") (pintype "passive"))
      (node (ref "SV11") (pin "5") (pinfunction "5_5") (pintype "passive"))
    )
    (net (code "108") (name "VSS") (class "Default")
      (node (ref "C1") (pin "-") (pinfunction "-_-") (pintype "passive"))
      (node (ref "C10") (pin "2") (pinfunction "2_2") (pintype "passive"))
      (node (ref "C2") (pin "-") (pinfunction "-_-") (pintype "passive"))
      (node (ref "C3") (pin "-") (pinfunction "-_-") (pintype "passive"))
      (node (ref "C4") (pin "-") (pinfunction "-_-") (pintype "passive"))
      (node (ref "C5") (pin "-") (pinfunction "-_-") (pintype "passive"))
      (node (ref "C6") (pin "2") (pinfunction "2_2") (pintype "passive"))
      (node (ref "C7") (pin "2") (pinfunction "2_2") (pintype "passive"))
      (node (ref "C8") (pin "2") (pinfunction "2_2") (pintype "passive"))
      (node (ref "C9") (pin "2") (pinfunction "2_2") (pintype "passive"))
      (node (ref "DC_IN") (pin "2") (pinfunction "2_2") (pintype "passive"))
      (node (ref "DC_IN2") (pin "2") (pinfunction "2_2") (pintype "passive"))
      (node (ref "DR1") (pin "3") (pinfunction "3_3") (pintype "passive"))
      (node (ref "IC1") (pin "1") (pinfunction "ADJ_1") (pintype "input"))
      (node (ref "IC2") (pin "1") (pinfunction "ADJ_1") (pintype "input"))
      (node (ref "IC3") (pin "1") (pinfunction "ADJ_1") (pintype "input"))
      (node (ref "JP5") (pin "3") (pinfunction "3_3") (pintype "passive"))
      (node (ref "JP5") (pin "4") (pinfunction "4_4") (pintype "passive"))
      (node (ref "JP6") (pin "3") (pinfunction "3_3") (pintype "passive"))
      (node (ref "LED9") (pin "C") (pinfunction "C_C") (pintype "passive"))
      (node (ref "Q1") (pin "2") (pinfunction "S_2") (pintype "passive"))
      (node (ref "R10") (pin "1") (pinfunction "1_1") (pintype "passive"))
      (node (ref "R11") (pin "1") (pinfunction "1_1") (pintype "passive"))
      (node (ref "R12") (pin "1") (pinfunction "1_1") (pintype "passive"))
      (node (ref "R13") (pin "1") (pinfunction "1_1") (pintype "passive"))
      (node (ref "R14") (pin "1") (pinfunction "1_1") (pintype "passive"))
      (node (ref "R15") (pin "1") (pinfunction "1_1") (pintype "passive"))
      (node (ref "R16") (pin "1") (pinfunction "1_1") (pintype "passive"))
      (node (ref "R17") (pin "A") (pinfunction "A_A") (pintype "passive"))
      (node (ref "R18") (pin "A") (pinfunction "A_A") (pintype "passive"))
      (node (ref "R19") (pin "1") (pinfunction "1_1") (pintype "passive"))
      (node (ref "R9") (pin "1") (pinfunction "1_1") (pintype "passive"))
      (node (ref "SV12") (pin "1") (pinfunction "1_1") (pintype "passive"))
      (node (ref "SV12") (pin "2") (pinfunction "2_2") (pintype "passive"))
      (node (ref "SV12") (pin "3") (pinfunction "3_3") (pintype "passive"))
      (node (ref "SV12") (pin "4") (pinfunction "4_4") (pintype "passive"))
      (node (ref "SV12") (pin "5") (pinfunction "5_5") (pintype "passive"))
      (node (ref "SV12") (pin "6") (pinfunction "6_6") (pintype "passive"))
      (node (ref "SV6") (pin "1") (pinfunction "1_1") (pintype "passive"))
      (node (ref "U$1") (pin "GND") (pinfunction "GND_GND") (pintype "bidirectional"))
    )
    (net (code "109") (name "unconnected-(S2-Pad2)") (class "Default")
      (node (ref "S2") (pin "2") (pinfunction "2_2") (pintype "passive"))
    )
    (net (code "110") (name "unconnected-(S2-Pad4)") (class "Default")
      (node (ref "S2") (pin "4") (pinfunction "4_4") (pintype "passive"))
    )
    (net (code "111") (name "unconnected-(S3-Pad2)") (class "Default")
      (node (ref "S3") (pin "2") (pinfunction "2_2") (pintype "passive"))
    )
    (net (code "112") (name "unconnected-(S3-Pad4)") (class "Default")
      (node (ref "S3") (pin "4") (pinfunction "4_4") (pintype "passive"))
    )
    (net (code "113") (name "unconnected-(S4-Pad2)") (class "Default")
      (node (ref "S4") (pin "2") (pinfunction "2_2") (pintype "passive"))
    )
    (net (code "114") (name "unconnected-(S4-Pad4)") (class "Default")
      (node (ref "S4") (pin "4") (pinfunction "4_4") (pintype "passive"))
    )
    (net (code "115") (name "unconnected-(S5-Pad2)") (class "Default")
      (node (ref "S5") (pin "2") (pinfunction "2_2") (pintype "passive"))
    )
    (net (code "116") (name "unconnected-(S5-Pad4)") (class "Default")
      (node (ref "S5") (pin "4") (pinfunction "4_4") (pintype "passive"))
    )
  )
)
